# ST_LINK_V2-1.net
KiCad netlist of a schematic drawn in Altium Designer
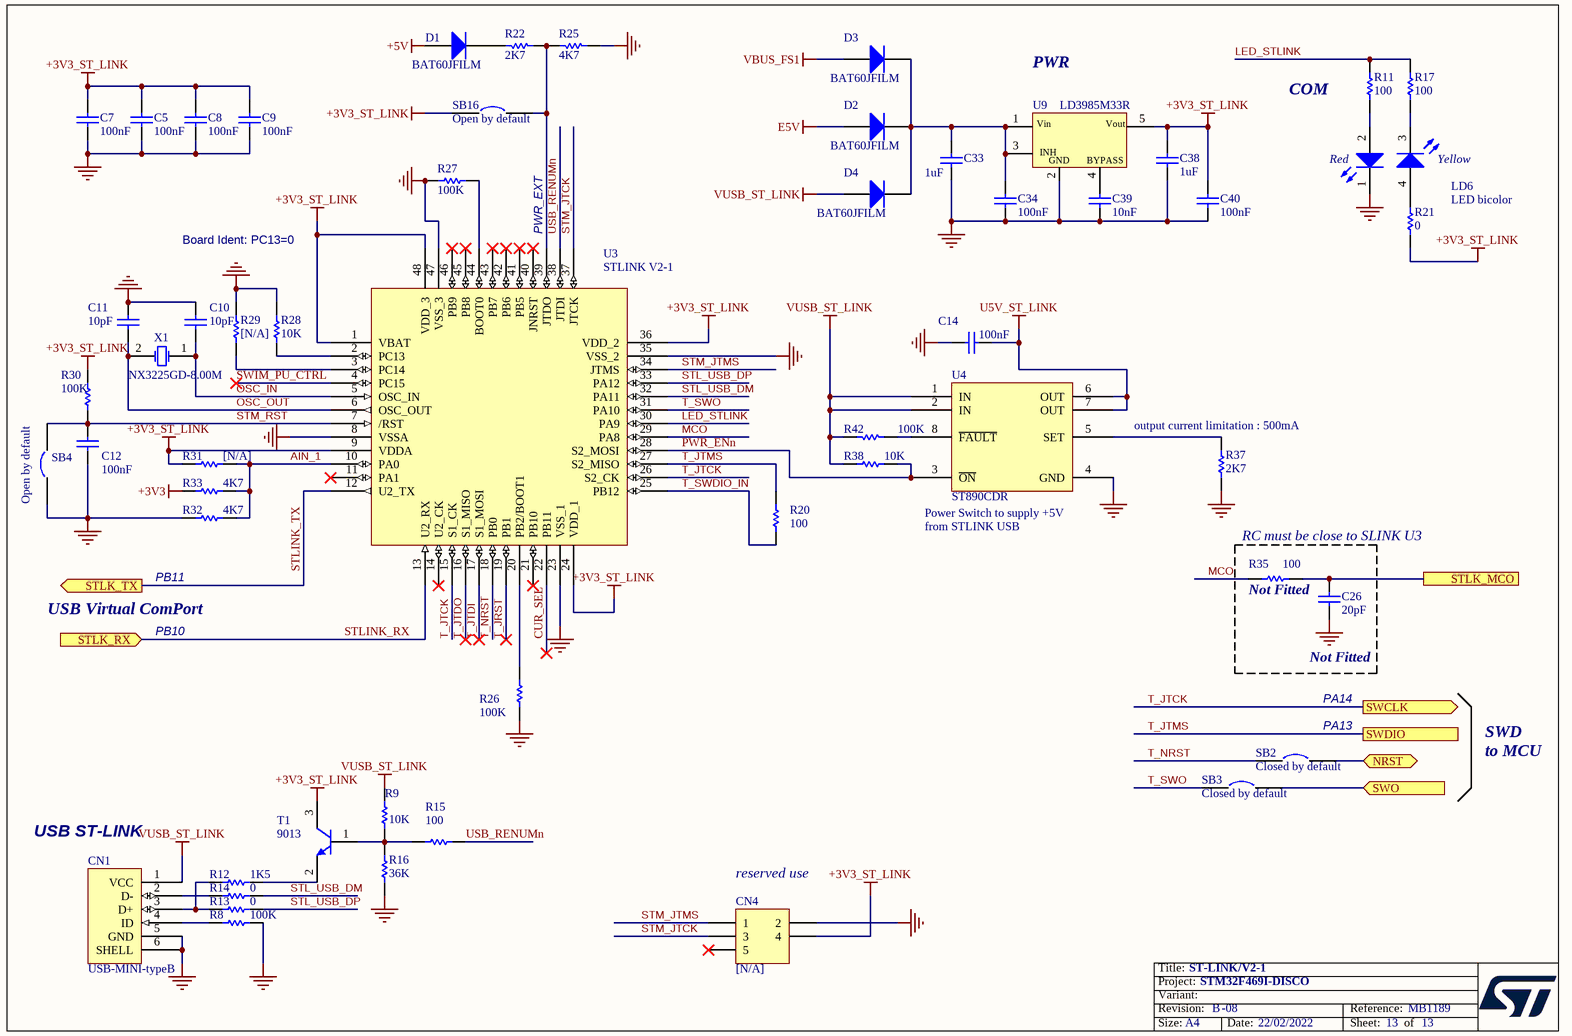
[diagram p0: ST_LINK_V2-1.SCHDOC]

(export (version "E")
  (design (tool "Eeschema 10.0.6"))
  (components
    (comp (ref "C5")
      (value "100nF")
      (footprint "0402C")
      (description "Capacitor 0402 / 0603 / 0805")
      (libsource (lib "MCD_TOOLS") (part "Capacitor_ST"))
    )
    (comp (ref "C7")
      (value "100nF")
      (footprint "0402C")
      (description "Capacitor 0402 / 0603 / 0805")
      (libsource (lib "MCD_TOOLS") (part "Capacitor_ST"))
    )
    (comp (ref "C8")
      (value "100nF")
      (footprint "0402C")
      (description "Capacitor 0402 / 0603 / 0805")
      (libsource (lib "MCD_TOOLS") (part "Capacitor_ST"))
    )
    (comp (ref "C9")
      (value "100nF")
      (footprint "0402C")
      (description "Capacitor 0402 / 0603 / 0805")
      (libsource (lib "MCD_TOOLS") (part "Capacitor_ST"))
    )
    (comp (ref "C10")
      (value "10pF")
      (footprint "0603C")
      (description "Capacitor 0402 / 0603 / 0805")
      (libsource (lib "MCD_TOOLS") (part "Capacitor_ST"))
    )
    (comp (ref "C11")
      (value "10pF")
      (footprint "0603C")
      (description "Capacitor 0402 / 0603 / 0805")
      (libsource (lib "MCD_TOOLS") (part "Capacitor_ST"))
    )
    (comp (ref "C12")
      (value "100nF")
      (footprint "0402C")
      (description "Capacitor 0402 / 0603 / 0805")
      (libsource (lib "MCD_TOOLS") (part "Capacitor_ST"))
    )
    (comp (ref "C14")
      (value "100nF")
      (footprint "0402C")
      (description "Capacitor 0402 / 0603 / 0805")
      (libsource (lib "MCD_TOOLS") (part "Capacitor_ST"))
    )
    (comp (ref "C26")
      (value "20pF")
      (footprint "0603C")
      (description "Capacitor,20pF,50V,NPO,5%,0402,YAGEO")
      (libsource (lib "MCD_TOOLS") (part "Cap_20pF_NPO_5%_0402"))
    )
    (comp (ref "C33")
      (value "1uF")
      (footprint "0603C")
      (description "Capacitor")
      (fields (field (name "TOLERANCE") "10%"))
      (libsource (lib "MB963_1") (part "CAP SMD 0603  X5R 1µF 25V 10%"))
    )
    (comp (ref "C34")
      (value "100nF")
      (footprint "0402C")
      (description "Capacitor 0402 / 0603 / 0805")
      (libsource (lib "MCD_TOOLS") (part "Capacitor_ST"))
    )
    (comp (ref "C38")
      (value "1uF")
      (footprint "0603C")
      (description "Capacitor")
      (fields (field (name "TOLERANCE") "10%"))
      (libsource (lib "MB963_1") (part "CAP SMD 0603  X5R 1µF 25V 10%"))
    )
    (comp (ref "C39")
      (value "10nF")
      (footprint "0603C")
      (description "0603  X7R 10NF")
      (fields (field (name "TOLERANCE") "10%"))
      (libsource (lib "MB963_1") (part "CAP SMD 0603  X7R 10000PF 50V 10%"))
    )
    (comp (ref "C40")
      (value "100nF")
      (footprint "0402C")
      (description "Capacitor 0402 / 0603 / 0805")
      (libsource (lib "MCD_TOOLS") (part "Capacitor_ST"))
    )
    (comp (ref "CN1")
      (value "USB-MINI-typeB")
      (footprint "MINIUSB_AB_5SM_RA")
      (description "USB-MINI-typeB connector")
      (libsource (lib "MCD_TOOLS") (part "USB-MINI-typeB connector"))
    )
    (comp (ref "CN4")
      (value "[N/A]")
      (footprint "HDR_2X3-1_2R54-6")
      (description "Header, 3-Pin, Dual row")
      (fields (field (name "PUBLISHER") "Altium Limited"))
      (libsource (lib "Miscellaneous Connectors") (part "Header 3X2"))
    )
    (comp (ref "D1")
      (value "BAT60JFILM")
      (footprint "SOD-323")
      (libsource (lib "MCD_TOOLS") (part "BAT60JFILM"))
    )
    (comp (ref "D2")
      (value "BAT60JFILM")
      (footprint "SOD-323")
      (libsource (lib "MCD_TOOLS") (part "BAT60JFILM"))
    )
    (comp (ref "D3")
      (value "BAT60JFILM")
      (footprint "SOD-323")
      (libsource (lib "MCD_TOOLS") (part "BAT60JFILM"))
    )
    (comp (ref "D4")
      (value "BAT60JFILM")
      (footprint "SOD-323")
      (libsource (lib "MCD_TOOLS") (part "BAT60JFILM"))
    )
    (comp (ref "LD6")
      (value "LED bicolor")
      (footprint "LED2_3528")
      (libsource (lib "MB819") (part "HSMF-A201-A00J1"))
    )
    (comp (ref "R8")
      (value "100K")
      (footprint "0603R")
      (description "Resistor")
      (fields (field (name "PUBLISHER") "Altium Limited"))
      (libsource (lib "Miscellaneous Devices") (part "res1"))
    )
    (comp (ref "R9")
      (value "10K")
      (footprint "0402R")
      (description "Resistor")
      (fields (field (name "PUBLISHER") "Altium Limited"))
      (libsource (lib "") (part "Res1_1"))
    )
    (comp (ref "R11")
      (value "100")
      (footprint "0603R")
      (description "Resistor")
      (fields (field (name "PUBLISHER") "Altium Limited"))
      (libsource (lib "") (part "Res1_1"))
    )
    (comp (ref "R12")
      (value "1K5")
      (footprint "0603R")
      (description "Resistor")
      (libsource (lib "Miscellaneous Devices") (part "Res1"))
    )
    (comp (ref "R13")
      (value "0")
      (footprint "0603R")
      (description "Resistor")
      (libsource (lib "Miscellaneous Devices") (part "Res1"))
    )
    (comp (ref "R14")
      (value "0")
      (footprint "0603R")
      (description "Resistor")
      (libsource (lib "Miscellaneous Devices") (part "Res1"))
    )
    (comp (ref "R15")
      (value "100")
      (footprint "0603R")
      (description "Resistor 0402 / 0603 / 0805")
      (libsource (lib "Miscellaneous Devices") (part "Res1"))
    )
    (comp (ref "R16")
      (value "36K")
      (footprint "0603R")
      (description "Resistor")
      (fields (field (name "PUBLISHER") "Altium Limited"))
      (libsource (lib "") (part "Res1_1"))
    )
    (comp (ref "R17")
      (value "100")
      (footprint "0603R")
      (description "Resistor")
      (fields (field (name "PUBLISHER") "Altium Limited"))
      (libsource (lib "") (part "Res1_1"))
    )
    (comp (ref "R20")
      (value "100")
      (footprint "STM-SMEE:0603R")
      (description "Resistor")
      (libsource (lib "MCD_TOOLS") (part "Resistor_ST"))
    )
    (comp (ref "R21")
      (value "0")
      (footprint "0603R")
      (description "Resistor")
      (fields (field (name "PUBLISHER") "Altium Limited"))
      (libsource (lib "") (part "Res1_1"))
    )
    (comp (ref "R22")
      (value "2K7")
      (footprint "0603R")
      (description "Resistor")
      (fields (field (name "PUBLISHER") "Altium Limited"))
      (libsource (lib "") (part "Res1_2"))
    )
    (comp (ref "R25")
      (value "4K7")
      (footprint "0603R")
      (description "Resistor")
      (fields (field (name "PUBLISHER") "Altium Limited"))
      (libsource (lib "") (part "Res1_2"))
    )
    (comp (ref "R26")
      (value "100K")
      (footprint "0603R")
      (description "Resistor 0402 / 0603 / 0805")
      (libsource (lib "Miscellaneous Devices") (part "Res1"))
    )
    (comp (ref "R27")
      (value "100K")
      (footprint "0603R")
      (description "Resistor 0402 / 0603 / 0805")
      (libsource (lib "Miscellaneous Devices") (part "Res1"))
    )
    (comp (ref "R28")
      (value "10K")
      (footprint "0402R")
      (description "Resistor")
      (libsource (lib "Miscellaneous Devices") (part "Res1"))
    )
    (comp (ref "R29")
      (value "[N/A]")
      (footprint "0603R")
      (description "Resistor 0402 / 0603 / 0805")
      (libsource (lib "Miscellaneous Devices") (part "Res1"))
    )
    (comp (ref "R30")
      (value "100K")
      (footprint "0603R")
      (description "Resistor 0402 / 0603 / 0805")
      (libsource (lib "Miscellaneous Devices") (part "Res1"))
    )
    (comp (ref "R31")
      (value "[N/A]")
      (footprint "0603R")
      (description "Resistor 0402 / 0603 / 0805")
      (libsource (lib "Miscellaneous Devices") (part "Res1"))
    )
    (comp (ref "R32")
      (value "4K7")
      (footprint "0603R")
      (description "Resistor 0402 / 0603 / 0805")
      (libsource (lib "Miscellaneous Devices") (part "Res1"))
    )
    (comp (ref "R33")
      (value "4K7")
      (footprint "0603R")
      (description "Resistor 0402 / 0603 / 0805")
      (libsource (lib "Miscellaneous Devices") (part "Res1"))
    )
    (comp (ref "R35")
      (value "100")
      (footprint "0603R")
      (description "Resistor 0402 / 0603 / 0805")
      (libsource (lib "Miscellaneous Devices") (part "Res1"))
    )
    (comp (ref "R37")
      (value "2K7")
      (footprint "STM-SMEE:0603R")
      (description "Resistor 0402 / 0603 / 0805")
      (libsource (lib "MCD_TOOLS") (part "Resistor_ST"))
    )
    (comp (ref "R38")
      (value "10K")
      (footprint "0402R")
      (description "Resistor")
      (libsource (lib "MCD_TOOLS") (part "Resistor_ST"))
    )
    (comp (ref "R42")
      (value "100K")
      (footprint "0603R")
      (description "Resistor")
      (fields (field (name "PUBLISHER") "Altium Limited"))
      (libsource (lib "*") (part "Res1"))
    )
    (comp (ref "SB2")
      (value "Closed by default")
      (footprint "SB_0603")
      (description "Circuit Breaker")
      (fields (field (name "PUBLISHER") "Altium Limited"))
      (libsource (lib "Miscellaneous Devices") (part "Circuit Breaker"))
    )
    (comp (ref "SB3")
      (value "Closed by default")
      (footprint "SB_0603")
      (description "Circuit Breaker")
      (fields (field (name "PUBLISHER") "Altium Limited"))
      (libsource (lib "Miscellaneous Devices") (part "Circuit Breaker"))
    )
    (comp (ref "SB4")
      (value "Open by default")
      (footprint "SB_0603")
      (description "Circuit Breaker")
      (fields (field (name "PUBLISHER") "Altium Limited"))
      (libsource (lib "Miscellaneous Devices") (part "Circuit Breaker"))
    )
    (comp (ref "SB16")
      (value "Open by default")
      (footprint "SB_0603")
      (description "Circuit Breaker")
      (fields (field (name "PUBLISHER") "Altium Limited"))
      (libsource (lib "Miscellaneous Devices") (part "Circuit Breaker"))
    )
    (comp (ref "T1")
      (value "9013")
      (footprint "SOT-23")
      (description "NPN Bipolar Transistor")
      (fields (field (name "PUBLISHER") "Altium Limited"))
      (libsource (lib "MB1167") (part "NPN"))
    )
    (comp (ref "U3")
      (value "STLINK V2-1")
      (footprint "LQFP48_0R5_9X9")
      (libsource (lib "*") (part "STM32F10x(48pin)"))
    )
    (comp (ref "U4")
      (value "ST890CDR")
      (footprint "SOIC8_1R27_4R9X6")
      (libsource (lib "MB1167") (part "ST890CDR"))
    )
    (comp (ref "U9")
      (value "LD3985M33R")
      (footprint "SOT23-5")
      (description "Ultra low drop-low noise BiCMOS voltage, regulators low ESR capacitors compatible")
      (libsource (lib "MCD_TOOLS") (part "LD3985M33R"))
    )
    (comp (ref "X1")
      (value "NX3225GD-8.00M")
      (footprint "XTAL_2SM_3R2X2R5_H1")
      (description "Crystal 8Mhz, 8pF, -+50PPM, SMD")
      (libsource (lib "MCD_TOOLS") (part "XTAL_8M_NX3225GD"))
    )
  )
  (nets
    (net (code "1") (name "+3V3") (class "Default")
      (node (ref "R33") (pin "1") (pinfunction "1_1") (pintype "passive"))
    )
    (net (code "2") (name "+3V3_ST_LINK") (class "Default")
      (node (ref "C38") (pin "1") (pinfunction "1_1") (pintype "passive"))
      (node (ref "C40") (pin "2") (pinfunction "2_2") (pintype "passive"))
      (node (ref "C5") (pin "2") (pinfunction "2_2") (pintype "passive"))
      (node (ref "C7") (pin "2") (pinfunction "2_2") (pintype "passive"))
      (node (ref "C8") (pin "2") (pinfunction "2_2") (pintype "passive"))
      (node (ref "C9") (pin "2") (pinfunction "2_2") (pintype "passive"))
      (node (ref "CN4") (pin "4") (pinfunction "4_4") (pintype "passive"))
      (node (ref "R21") (pin "2") (pinfunction "2_2") (pintype "passive"))
      (node (ref "R30") (pin "2") (pinfunction "2_2") (pintype "passive"))
      (node (ref "R31") (pin "1") (pinfunction "1_1") (pintype "passive"))
      (node (ref "SB16") (pin "1") (pinfunction "1_1") (pintype "passive"))
      (node (ref "T1") (pin "3") (pinfunction "C_3") (pintype "passive"))
      (node (ref "U3") (pin "1") (pinfunction "VBAT_1") (pintype "power_in"))
      (node (ref "U3") (pin "24") (pinfunction "VDD_1_24") (pintype "power_in"))
      (node (ref "U3") (pin "36") (pinfunction "VDD_2_36") (pintype "power_in"))
      (node (ref "U3") (pin "48") (pinfunction "VDD_3_48") (pintype "power_in"))
      (node (ref "U3") (pin "9") (pinfunction "VDDA_9") (pintype "power_in"))
      (node (ref "U9") (pin "5") (pinfunction "Vout_5") (pintype "passive"))
    )
    (net (code "3") (name "+5V") (class "Default")
      (node (ref "D1") (pin "1") (pinfunction "A_1") (pintype "passive"))
    )
    (net (code "4") (name "/AIN_1") (class "Default")
      (node (ref "R31") (pin "2") (pinfunction "2_2") (pintype "passive"))
      (node (ref "R32") (pin "2") (pinfunction "2_2") (pintype "passive"))
      (node (ref "R33") (pin "2") (pinfunction "2_2") (pintype "passive"))
      (node (ref "U3") (pin "10") (pinfunction "PA0_10") (pintype "bidirectional"))
    )
    (net (code "5") (name "/CUR_SEL") (class "Default")
      (node (ref "U3") (pin "22") (pinfunction "PB11_22") (pintype "passive+no_connect"))
    )
    (net (code "6") (name "/LED_STLINK") (class "Default")
      (node (ref "R11") (pin "1") (pinfunction "1_1") (pintype "passive"))
      (node (ref "R17") (pin "1") (pinfunction "1_1") (pintype "passive"))
      (node (ref "U3") (pin "30") (pinfunction "PA9_30") (pintype "bidirectional"))
    )
    (net (code "7") (name "/MCO") (class "Default")
      (node (ref "R35") (pin "1") (pinfunction "1_1") (pintype "passive"))
      (node (ref "U3") (pin "29") (pinfunction "PA8_29") (pintype "bidirectional"))
    )
    (net (code "8") (name "/NRST") (class "Default")
      (node (ref "SB2") (pin "2") (pinfunction "2_2") (pintype "passive"))
    )
    (net (code "9") (name "/OSC_IN") (class "Default")
      (node (ref "C10") (pin "1") (pinfunction "1_1") (pintype "passive"))
      (node (ref "U3") (pin "5") (pinfunction "OSC_IN_5") (pintype "input"))
      (node (ref "X1") (pin "1") (pinfunction "OSC1_1") (pintype "passive"))
    )
    (net (code "10") (name "/OSC_OUT") (class "Default")
      (node (ref "C11") (pin "1") (pinfunction "1_1") (pintype "passive"))
      (node (ref "U3") (pin "6") (pinfunction "OSC_OUT_6") (pintype "output"))
      (node (ref "X1") (pin "2") (pinfunction "OSC2_2") (pintype "passive"))
    )
    (net (code "11") (name "/PWR_ENn") (class "Default")
      (node (ref "R38") (pin "2") (pinfunction "2_2") (pintype "passive"))
      (node (ref "U3") (pin "28") (pinfunction "S2_MOSI_28") (pintype "bidirectional"))
      (node (ref "U4") (pin "3") (pinfunction "~{ON}_3") (pintype "passive"))
    )
    (net (code "12") (name "/STLINK_RX") (class "Default")
      (node (ref "U3") (pin "13") (pinfunction "U2_RX_13") (pintype "input"))
    )
    (net (code "13") (name "/STLINK_TX") (class "Default")
      (node (ref "U3") (pin "12") (pinfunction "U2_TX_12") (pintype "output"))
    )
    (net (code "14") (name "/STLK_MCO") (class "Default")
      (node (ref "C26") (pin "1") (pinfunction "1_1") (pintype "passive"))
      (node (ref "R35") (pin "2") (pinfunction "2_2") (pintype "passive"))
    )
    (net (code "15") (name "/STL_USB_DM") (class "Default")
      (node (ref "R14") (pin "2") (pinfunction "2_2") (pintype "passive"))
      (node (ref "U3") (pin "32") (pinfunction "PA11_32") (pintype "bidirectional"))
    )
    (net (code "16") (name "/STL_USB_DP") (class "Default")
      (node (ref "R13") (pin "2") (pinfunction "2_2") (pintype "passive"))
      (node (ref "U3") (pin "33") (pinfunction "PA12_33") (pintype "bidirectional"))
    )
    (net (code "17") (name "/STM_JTCK") (class "Default")
      (node (ref "CN4") (pin "3") (pinfunction "3_3") (pintype "passive"))
      (node (ref "U3") (pin "37") (pinfunction "JTCK_37") (pintype "bidirectional"))
    )
    (net (code "18") (name "/STM_JTMS") (class "Default")
      (node (ref "CN4") (pin "1") (pinfunction "1_1") (pintype "passive"))
      (node (ref "U3") (pin "34") (pinfunction "JTMS_34") (pintype "bidirectional"))
    )
    (net (code "19") (name "/STM_RST") (class "Default")
      (node (ref "C12") (pin "2") (pinfunction "2_2") (pintype "passive"))
      (node (ref "R30") (pin "1") (pinfunction "1_1") (pintype "passive"))
      (node (ref "SB4") (pin "2") (pinfunction "2_2") (pintype "passive"))
      (node (ref "U3") (pin "7") (pinfunction "/RST_7") (pintype "input"))
    )
    (net (code "20") (name "/SWIM_PU_CTRL") (class "Default")
      (node (ref "U3") (pin "4") (pinfunction "PC15_4") (pintype "bidirectional+no_connect"))
    )
    (net (code "21") (name "/SWO") (class "Default")
      (node (ref "SB3") (pin "2") (pinfunction "2_2") (pintype "passive"))
    )
    (net (code "22") (name "/T_JRST") (class "Default")
      (node (ref "U3") (pin "19") (pinfunction "PB1_19") (pintype "bidirectional+no_connect"))
    )
    (net (code "23") (name "/T_JTCK") (class "Default")
      (node (ref "U3") (pin "15") (pinfunction "S1_CK_15") (pintype "bidirectional"))
      (node (ref "U3") (pin "26") (pinfunction "S2_CK_26") (pintype "bidirectional"))
    )
    (net (code "24") (name "/T_JTDI") (class "Default")
      (node (ref "U3") (pin "17") (pinfunction "S1_MOSI_17") (pintype "bidirectional+no_connect"))
    )
    (net (code "25") (name "/T_JTDO") (class "Default")
      (node (ref "U3") (pin "16") (pinfunction "S1_MISO_16") (pintype "bidirectional+no_connect"))
    )
    (net (code "26") (name "/T_JTMS") (class "Default")
      (node (ref "R20") (pin "2") (pinfunction "2_2") (pintype "passive"))
      (node (ref "U3") (pin "27") (pinfunction "S2_MISO_27") (pintype "bidirectional"))
    )
    (net (code "27") (name "/T_NRST") (class "Default")
      (node (ref "SB2") (pin "1") (pinfunction "1_1") (pintype "passive"))
      (node (ref "U3") (pin "18") (pinfunction "PB0_18") (pintype "bidirectional"))
    )
    (net (code "28") (name "/T_SWDIO_IN") (class "Default")
      (node (ref "R20") (pin "1") (pinfunction "1_1") (pintype "passive"))
      (node (ref "U3") (pin "25") (pinfunction "PB12_25") (pintype "bidirectional"))
    )
    (net (code "29") (name "/T_SWO") (class "Default")
      (node (ref "SB3") (pin "1") (pinfunction "1_1") (pintype "passive"))
      (node (ref "U3") (pin "31") (pinfunction "PA10_31") (pintype "bidirectional"))
    )
    (net (code "30") (name "/USB_RENUMn") (class "Default")
      (node (ref "R15") (pin "2") (pinfunction "2_2") (pintype "passive"))
      (node (ref "U3") (pin "38") (pinfunction "JTDI_38") (pintype "bidirectional"))
    )
    (net (code "31") (name "E5V") (class "Default")
      (node (ref "D2") (pin "1") (pinfunction "A_1") (pintype "passive"))
    )
    (net (code "32") (name "GND") (class "Default")
      (node (ref "C10") (pin "2") (pinfunction "2_2") (pintype "passive"))
      (node (ref "C11") (pin "2") (pinfunction "2_2") (pintype "passive"))
      (node (ref "C12") (pin "1") (pinfunction "1_1") (pintype "passive"))
      (node (ref "C14") (pin "1") (pinfunction "1_1") (pintype "passive"))
      (node (ref "C26") (pin "2") (pinfunction "2_2") (pintype "passive"))
      (node (ref "C33") (pin "1") (pinfunction "1_1") (pintype "passive"))
      (node (ref "C34") (pin "1") (pinfunction "1_1") (pintype "passive"))
      (node (ref "C38") (pin "2") (pinfunction "2_2") (pintype "passive"))
      (node (ref "C39") (pin "1") (pinfunction "1_1") (pintype "passive"))
      (node (ref "C40") (pin "1") (pinfunction "1_1") (pintype "passive"))
      (node (ref "C5") (pin "1") (pinfunction "1_1") (pintype "passive"))
      (node (ref "C7") (pin "1") (pinfunction "1_1") (pintype "passive"))
      (node (ref "C8") (pin "1") (pinfunction "1_1") (pintype "passive"))
      (node (ref "C9") (pin "1") (pinfunction "1_1") (pintype "passive"))
      (node (ref "CN1") (pin "5") (pinfunction "GND_5") (pintype "passive"))
      (node (ref "CN1") (pin "6") (pinfunction "SHELL_6") (pintype "passive"))
      (node (ref "CN4") (pin "2") (pinfunction "2_2") (pintype "passive"))
      (node (ref "LD6") (pin "1") (pinfunction "RED_cathode_1") (pintype "passive"))
      (node (ref "R16") (pin "1") (pinfunction "1_1") (pintype "passive"))
      (node (ref "R25") (pin "2") (pinfunction "2_2") (pintype "passive"))
      (node (ref "R26") (pin "1") (pinfunction "1_1") (pintype "passive"))
      (node (ref "R27") (pin "1") (pinfunction "1_1") (pintype "passive"))
      (node (ref "R28") (pin "1") (pinfunction "1_1") (pintype "passive"))
      (node (ref "R29") (pin "1") (pinfunction "1_1") (pintype "passive"))
      (node (ref "R32") (pin "1") (pinfunction "1_1") (pintype "passive"))
      (node (ref "R37") (pin "2") (pinfunction "2_2") (pintype "passive"))
      (node (ref "R8") (pin "2") (pinfunction "2_2") (pintype "passive"))
      (node (ref "SB4") (pin "1") (pinfunction "1_1") (pintype "passive"))
      (node (ref "U3") (pin "23") (pinfunction "VSS_1_23") (pintype "passive"))
      (node (ref "U3") (pin "35") (pinfunction "VSS_2_35") (pintype "passive"))
      (node (ref "U3") (pin "47") (pinfunction "VSS_3_47") (pintype "passive"))
      (node (ref "U3") (pin "8") (pinfunction "VSSA_8") (pintype "passive"))
      (node (ref "U4") (pin "4") (pinfunction "GND_4") (pintype "passive"))
      (node (ref "U9") (pin "2") (pinfunction "GND_2") (pintype "passive"))
    )
    (net (code "33") (name "Net-(CN1-D+)") (class "Default")
      (node (ref "CN1") (pin "3") (pinfunction "D+_3") (pintype "bidirectional"))
      (node (ref "R12") (pin "1") (pinfunction "1_1") (pintype "passive"))
      (node (ref "R13") (pin "1") (pinfunction "1_1") (pintype "passive"))
    )
    (net (code "34") (name "Net-(CN1-D-)") (class "Default")
      (node (ref "CN1") (pin "2") (pinfunction "D-_2") (pintype "bidirectional"))
      (node (ref "R14") (pin "1") (pinfunction "1_1") (pintype "passive"))
    )
    (net (code "35") (name "Net-(CN1-ID)") (class "Default")
      (node (ref "CN1") (pin "4") (pinfunction "ID_4") (pintype "input"))
      (node (ref "R8") (pin "1") (pinfunction "1_1") (pintype "passive"))
    )
    (net (code "36") (name "Net-(D1-K)") (class "Default")
      (node (ref "D1") (pin "2") (pinfunction "K_2") (pintype "passive"))
      (node (ref "R22") (pin "1") (pinfunction "1_1") (pintype "passive"))
    )
    (net (code "37") (name "Net-(D2-K)") (class "Default")
      (node (ref "C33") (pin "2") (pinfunction "2_2") (pintype "passive"))
      (node (ref "C34") (pin "2") (pinfunction "2_2") (pintype "passive"))
      (node (ref "D2") (pin "2") (pinfunction "K_2") (pintype "passive"))
      (node (ref "D3") (pin "2") (pinfunction "K_2") (pintype "passive"))
      (node (ref "D4") (pin "2") (pinfunction "K_2") (pintype "passive"))
      (node (ref "U9") (pin "1") (pinfunction "Vin_1") (pintype "passive"))
      (node (ref "U9") (pin "3") (pinfunction "CE_3") (pintype "passive"))
    )
    (net (code "38") (name "Net-(LD6-Red_anode)") (class "Default")
      (node (ref "LD6") (pin "2") (pinfunction "Red_anode_2") (pintype "passive"))
      (node (ref "R11") (pin "2") (pinfunction "2_2") (pintype "passive"))
    )
    (net (code "39") (name "Net-(LD6-YellowGreen_anode)") (class "Default")
      (node (ref "LD6") (pin "4") (pinfunction "YellowGreen_anode_4") (pintype "passive"))
      (node (ref "R21") (pin "1") (pinfunction "1_1") (pintype "passive"))
    )
    (net (code "40") (name "Net-(LD6-YellowGreen_cathode)") (class "Default")
      (node (ref "LD6") (pin "3") (pinfunction "YellowGreen_cathode_3") (pintype "passive"))
      (node (ref "R17") (pin "2") (pinfunction "2_2") (pintype "passive"))
    )
    (net (code "41") (name "Net-(T1-B)") (class "Default")
      (node (ref "R15") (pin "1") (pinfunction "1_1") (pintype "passive"))
      (node (ref "R16") (pin "2") (pinfunction "2_2") (pintype "passive"))
      (node (ref "R9") (pin "1") (pinfunction "1_1") (pintype "passive"))
      (node (ref "T1") (pin "1") (pinfunction "B_1") (pintype "passive"))
    )
    (net (code "42") (name "Net-(T1-E)") (class "Default")
      (node (ref "R12") (pin "2") (pinfunction "2_2") (pintype "passive"))
      (node (ref "T1") (pin "2") (pinfunction "E_2") (pintype "passive"))
    )
    (net (code "43") (name "Net-(U3-BOOT0)") (class "Default")
      (node (ref "R27") (pin "2") (pinfunction "2_2") (pintype "passive"))
      (node (ref "U3") (pin "44") (pinfunction "BOOT0_44") (pintype "bidirectional"))
    )
    (net (code "44") (name "Net-(U3-JTDO)") (class "Default")
      (node (ref "R22") (pin "2") (pinfunction "2_2") (pintype "passive"))
      (node (ref "R25") (pin "1") (pinfunction "1_1") (pintype "passive"))
      (node (ref "SB16") (pin "2") (pinfunction "2_2") (pintype "passive"))
      (node (ref "U3") (pin "39") (pinfunction "JTDO_39") (pintype "bidirectional"))
    )
    (net (code "45") (name "Net-(U3-PB2{slash}BOOT1)") (class "Default")
      (node (ref "R26") (pin "2") (pinfunction "2_2") (pintype "passive"))
      (node (ref "U3") (pin "20") (pinfunction "PB2/BOOT1_20") (pintype "passive"))
    )
    (net (code "46") (name "Net-(U3-PC13)") (class "Default")
      (node (ref "R28") (pin "2") (pinfunction "2_2") (pintype "passive"))
      (node (ref "U3") (pin "2") (pinfunction "PC13_2") (pintype "bidirectional"))
    )
    (net (code "47") (name "Net-(U3-PC14)") (class "Default")
      (node (ref "R29") (pin "2") (pinfunction "2_2") (pintype "passive"))
      (node (ref "U3") (pin "3") (pinfunction "PC14_3") (pintype "bidirectional"))
    )
    (net (code "48") (name "Net-(U4-SET)") (class "Default")
      (node (ref "R37") (pin "1") (pinfunction "1_1") (pintype "passive"))
      (node (ref "U4") (pin "5") (pinfunction "SET_5") (pintype "passive"))
    )
    (net (code "49") (name "Net-(U4-~{FAULT})") (class "Default")
      (node (ref "R42") (pin "2") (pinfunction "2_2") (pintype "passive"))
      (node (ref "U4") (pin "8") (pinfunction "~{FAULT}_8") (pintype "passive"))
    )
    (net (code "50") (name "Net-(U9-BYPASS)") (class "Default")
      (node (ref "C39") (pin "2") (pinfunction "2_2") (pintype "passive"))
      (node (ref "U9") (pin "4") (pinfunction "BYPASS_4") (pintype "passive"))
    )
    (net (code "51") (name "U5V_ST_LINK") (class "Default")
      (node (ref "C14") (pin "2") (pinfunction "2_2") (pintype "passive"))
      (node (ref "U4") (pin "6") (pinfunction "OUT_6") (pintype "passive"))
      (node (ref "U4") (pin "7") (pinfunction "OUT_7") (pintype "passive"))
    )
    (net (code "52") (name "VBUS_FS1") (class "Default")
      (node (ref "D3") (pin "1") (pinfunction "A_1") (pintype "passive"))
    )
    (net (code "53") (name "VUSB_ST_LINK") (class "Default")
      (node (ref "CN1") (pin "1") (pinfunction "VCC_1") (pintype "power_in"))
      (node (ref "D4") (pin "1") (pinfunction "A_1") (pintype "passive"))
      (node (ref "R38") (pin "1") (pinfunction "1_1") (pintype "passive"))
      (node (ref "R42") (pin "1") (pinfunction "1_1") (pintype "passive"))
      (node (ref "R9") (pin "2") (pinfunction "2_2") (pintype "passive"))
      (node (ref "U4") (pin "1") (pinfunction "IN_1") (pintype "passive"))
      (node (ref "U4") (pin "2") (pinfunction "IN_2") (pintype "passive"))
    )
    (net (code "54") (name "unconnected-(CN4-Pad5)") (class "Default")
      (node (ref "CN4") (pin "5") (pinfunction "5_5") (pintype "passive+no_connect"))
    )
    (net (code "55") (name "unconnected-(U3-JNRST-Pad40)") (class "Default")
      (node (ref "U3") (pin "40") (pinfunction "JNRST_40") (pintype "bidirectional+no_connect"))
    )
    (net (code "56") (name "unconnected-(U3-PA1-Pad11)") (class "Default")
      (node (ref "U3") (pin "11") (pinfunction "PA1_11") (pintype "bidirectional+no_connect"))
    )
    (net (code "57") (name "unconnected-(U3-PB5-Pad41)") (class "Default")
      (node (ref "U3") (pin "41") (pinfunction "PB5_41") (pintype "bidirectional+no_connect"))
    )
    (net (code "58") (name "unconnected-(U3-PB6-Pad42)") (class "Default")
      (node (ref "U3") (pin "42") (pinfunction "PB6_42") (pintype "bidirectional+no_connect"))
    )
    (net (code "59") (name "unconnected-(U3-PB7-Pad43)") (class "Default")
      (node (ref "U3") (pin "43") (pinfunction "PB7_43") (pintype "bidirectional+no_connect"))
    )
    (net (code "60") (name "unconnected-(U3-PB8-Pad45)") (class "Default")
      (node (ref "U3") (pin "45") (pinfunction "PB8_45") (pintype "bidirectional+no_connect"))
    )
    (net (code "61") (name "unconnected-(U3-PB9-Pad46)") (class "Default")
      (node (ref "U3") (pin "46") (pinfunction "PB9_46") (pintype "bidirectional+no_connect"))
    )
    (net (code "62") (name "unconnected-(U3-PB10-Pad21)") (class "Default")
      (node (ref "U3") (pin "21") (pinfunction "PB10_21") (pintype "bidirectional+no_connect"))
    )
    (net (code "63") (name "unconnected-(U3-U2_CK-Pad14)") (class "Default")
      (node (ref "U3") (pin "14") (pinfunction "U2_CK_14") (pintype "bidirectional+no_connect"))
    )
  )
)
